# STC89C52.net
KiCad netlist of a schematic drawn in Altium Designer
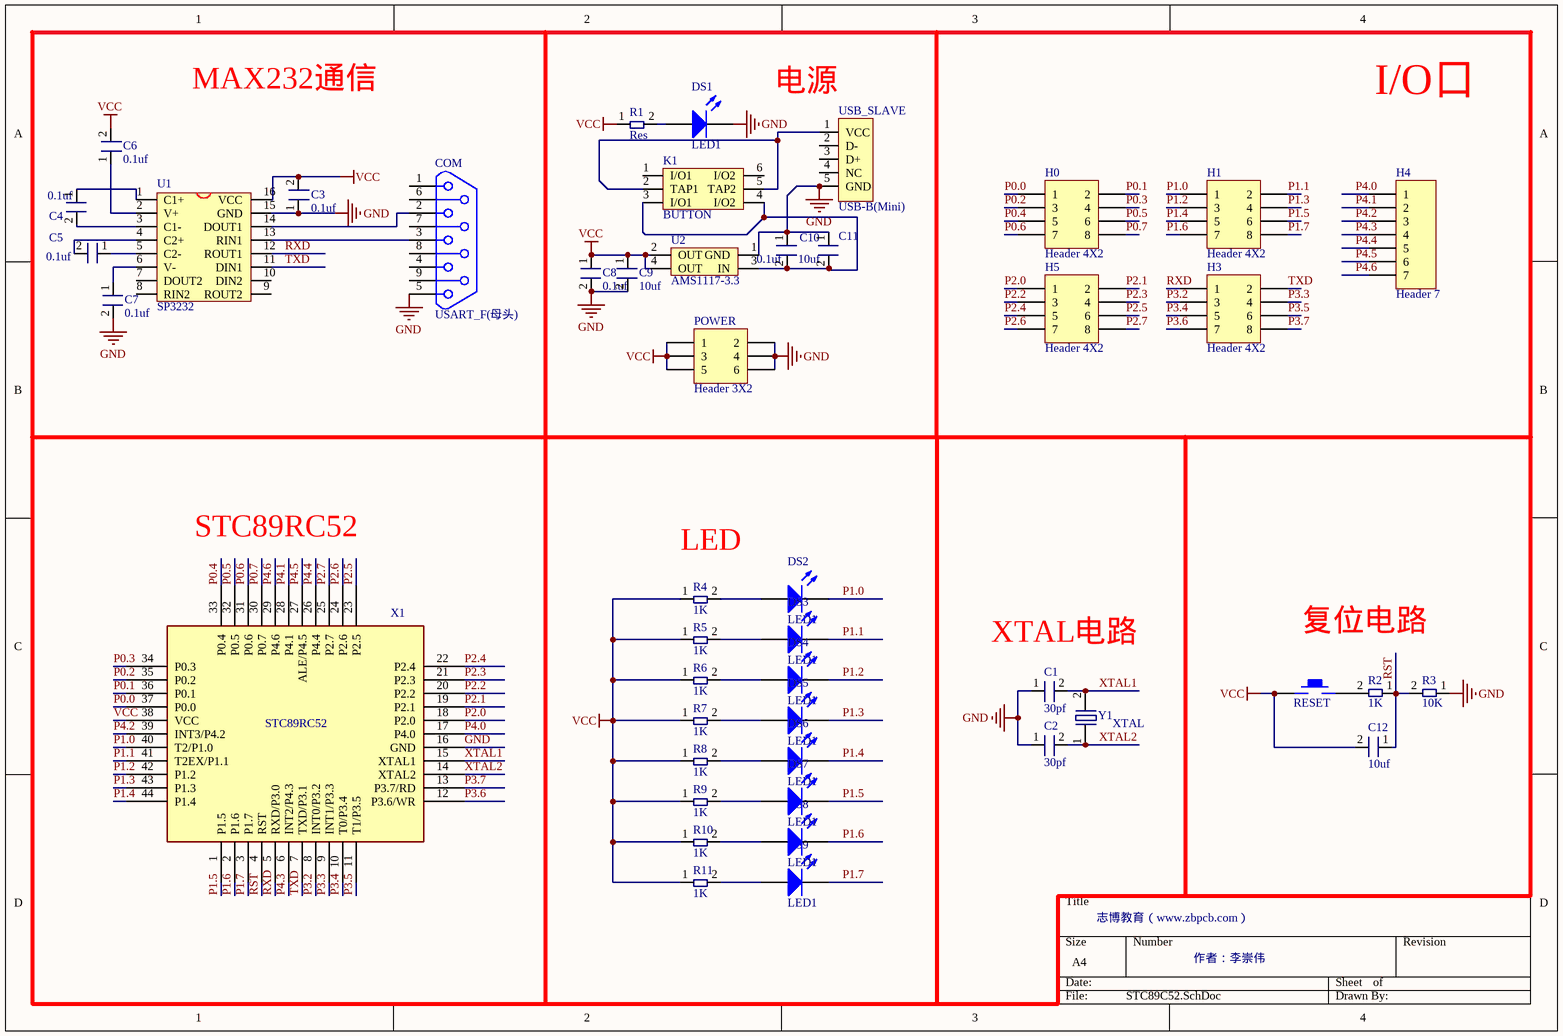
[diagram p0: STC89C52.SchDoc]

(export (version "E")
  (design (tool "Eeschema 10.0.6"))
  (components
    (comp (ref "C1") (value "30pf") (footprint "Cap") (libsource (lib "STC89C52") (part "Cap")))
    (comp (ref "C2") (value "30pf") (footprint "Cap") (libsource (lib "STC89C52") (part "Cap")))
    (comp (ref "C3") (value "0.1uf") (footprint "Cap") (libsource (lib "STC89C52") (part "Cap")))
    (comp (ref "C4") (value "0.1uf") (footprint "Cap") (libsource (lib "STC89C52") (part "Cap")))
    (comp (ref "C5") (value "0.1uf") (footprint "Cap") (libsource (lib "STC89C52") (part "Cap")))
    (comp (ref "C6") (value "0.1uf") (footprint "Cap") (libsource (lib "STC89C52") (part "Cap")))
    (comp (ref "C7") (value "0.1uf") (footprint "Cap") (libsource (lib "STC89C52") (part "Cap")))
    (comp (ref "C8") (value "0.1uf") (footprint "Cap") (libsource (lib "STC89C52") (part "Cap")))
    (comp (ref "C9") (value "10uf") (footprint "Cap") (libsource (lib "STC89C52") (part "Cap")))
    (comp (ref "C10") (value "0.1uf") (footprint "Cap") (libsource (lib "STC89C52") (part "Cap")))
    (comp (ref "C11") (value "10uf") (footprint "Cap") (libsource (lib "STC89C52") (part "Cap")))
    (comp (ref "C12") (value "10uf") (footprint "Cap") (libsource (lib "STC89C52") (part "Cap")))
    (comp (ref "COM") (value "USART_F(母头)") (footprint "DB9") (libsource (lib "STM32F407封装库") (part "DB9")))
    (comp (ref "DS1")
      (value "LED1")
      (footprint "SMDLED")
      (description "Typical RED, GREEN, YELLOW, AMBER GaAs LED")
      (fields (field (name "PUBLISHER") "Altium Limited"))
      (libsource (lib "STM32F407封装库") (part "LED2"))
    )
    (comp (ref "DS2")
      (value "LED1")
      (footprint "SMDLED")
      (description "Typical RED, GREEN, YELLOW, AMBER GaAs LED")
      (fields (field (name "PUBLISHER") "Altium Limited"))
      (libsource (lib "STM32F407封装库") (part "LED2"))
    )
    (comp (ref "DS3")
      (value "LED1")
      (footprint "SMDLED")
      (description "Typical RED, GREEN, YELLOW, AMBER GaAs LED")
      (fields (field (name "PUBLISHER") "Altium Limited"))
      (libsource (lib "STM32F407封装库") (part "LED2"))
    )
    (comp (ref "DS4")
      (value "LED1")
      (footprint "SMDLED")
      (description "Typical RED, GREEN, YELLOW, AMBER GaAs LED")
      (fields (field (name "PUBLISHER") "Altium Limited"))
      (libsource (lib "STM32F407封装库") (part "LED2"))
    )
    (comp (ref "DS5")
      (value "LED1")
      (footprint "SMDLED")
      (description "Typical RED, GREEN, YELLOW, AMBER GaAs LED")
      (fields (field (name "PUBLISHER") "Altium Limited"))
      (libsource (lib "STM32F407封装库") (part "LED2"))
    )
    (comp (ref "DS6")
      (value "LED1")
      (footprint "SMDLED")
      (description "Typical RED, GREEN, YELLOW, AMBER GaAs LED")
      (fields (field (name "PUBLISHER") "Altium Limited"))
      (libsource (lib "STM32F407封装库") (part "LED2"))
    )
    (comp (ref "DS7")
      (value "LED1")
      (footprint "SMDLED")
      (description "Typical RED, GREEN, YELLOW, AMBER GaAs LED")
      (fields (field (name "PUBLISHER") "Altium Limited"))
      (libsource (lib "STM32F407封装库") (part "LED2"))
    )
    (comp (ref "DS8")
      (value "LED1")
      (footprint "SMDLED")
      (description "Typical RED, GREEN, YELLOW, AMBER GaAs LED")
      (fields (field (name "PUBLISHER") "Altium Limited"))
      (libsource (lib "STM32F407封装库") (part "LED2"))
    )
    (comp (ref "DS9")
      (value "LED1")
      (footprint "SMDLED")
      (description "Typical RED, GREEN, YELLOW, AMBER GaAs LED")
      (fields (field (name "PUBLISHER") "Altium Limited"))
      (libsource (lib "STM32F407封装库") (part "LED2"))
    )
    (comp (ref "H0")
      (value "Header 4X2")
      (footprint "HDR2X4")
      (description "Header, 4-Pin, Dual row")
      (fields (field (name "PUBLISHER") "Altium Limited"))
      (libsource (lib "Miscellaneous Connectors") (part "Header 4X2"))
    )
    (comp (ref "H1")
      (value "Header 4X2")
      (footprint "HDR2X4")
      (description "Header, 4-Pin, Dual row")
      (fields (field (name "PUBLISHER") "Altium Limited"))
      (libsource (lib "Miscellaneous Connectors") (part "Header 4X2"))
    )
    (comp (ref "H3")
      (value "Header 4X2")
      (footprint "HDR2X4")
      (description "Header, 4-Pin, Dual row")
      (fields (field (name "PUBLISHER") "Altium Limited"))
      (libsource (lib "Miscellaneous Connectors") (part "Header 4X2"))
    )
    (comp (ref "H4")
      (value "Header 7")
      (footprint "HDR1X7")
      (description "Header, 7-Pin")
      (fields (field (name "PUBLISHER") "Altium Limited"))
      (libsource (lib "Miscellaneous Connectors") (part "Header 7"))
    )
    (comp (ref "H5")
      (value "Header 4X2")
      (footprint "HDR2X4")
      (description "Header, 4-Pin, Dual row")
      (fields (field (name "PUBLISHER") "Altium Limited"))
      (libsource (lib "Miscellaneous Connectors") (part "Header 4X2"))
    )
    (comp (ref "K1")
      (value "BUTTON")
      (footprint "BTN8.5*8.5")
      (libsource (lib "STM32F407封装库") (part "BUTTON"))
    )
    (comp (ref "POWER")
      (value "Header 3X2")
      (footprint "HDR2X3")
      (description "Header, 3-Pin, Dual row")
      (fields (field (name "PUBLISHER") "Altium Limited"))
      (libsource (lib "STM32F407封装库") (part "Header 3X2"))
    )
    (comp (ref "R1") (value "Res") (footprint "Cap") (libsource (lib "STC89C52") (part "Res")))
    (comp (ref "R2") (value "1K") (footprint "Cap") (libsource (lib "STC89C52") (part "Res")))
    (comp (ref "R3") (value "10K") (footprint "Cap") (libsource (lib "STC89C52") (part "Res")))
    (comp (ref "R4") (value "1K") (footprint "Cap") (libsource (lib "STC89C52") (part "Res")))
    (comp (ref "R5") (value "1K") (footprint "Cap") (libsource (lib "STC89C52") (part "Res")))
    (comp (ref "R6") (value "1K") (footprint "Cap") (libsource (lib "STC89C52") (part "Res")))
    (comp (ref "R7") (value "1K") (footprint "Cap") (libsource (lib "STC89C52") (part "Res")))
    (comp (ref "R8") (value "1K") (footprint "Cap") (libsource (lib "STC89C52") (part "Res")))
    (comp (ref "R9") (value "1K") (footprint "Cap") (libsource (lib "STC89C52") (part "Res")))
    (comp (ref "R10") (value "1K") (footprint "Cap") (libsource (lib "STC89C52") (part "Res")))
    (comp (ref "R11") (value "1K") (footprint "Cap") (libsource (lib "STC89C52") (part "Res")))
    (comp (ref "RESET") (value "KEY_M") (footprint "KEY_M") (libsource (lib "STM32F407封装库") (part "KEY_M")))
    (comp (ref "U1") (value "SP3232") (footprint "SOP16M") (libsource (lib "STM32F407封装库") (part "MAX3232")))
    (comp (ref "U2")
      (value "AMS1117-3.3")
      (footprint "AMS1117")
      (libsource (lib "STM32F407封装库") (part "AMS1117"))
    )
    (comp (ref "USB_SLAVE")
      (value "USB-B(Mini)")
      (footprint "USB/SM0.8-6H5")
      (libsource (lib "STM32F407封装库") (part "USB5"))
    )
    (comp (ref "X1")
      (value "STC89RC52")
      (footprint "STC89C52")
      (libsource (lib "STC89C52") (part "STC89RC52"))
    )
    (comp (ref "Y1") (value "XTAL") (footprint "XTAL") (libsource (lib "STC89C52") (part "XTAL")))
  )
  (nets
    (net (code "1") (name "/P0.0") (class "Default")
      (node (ref "H0") (pin "1") (pinfunction "1_1") (pintype "passive"))
      (node (ref "X1") (pin "37") (pinfunction "P0.0_37") (pintype "passive"))
    )
    (net (code "2") (name "/P0.1") (class "Default")
      (node (ref "H0") (pin "2") (pinfunction "2_2") (pintype "passive"))
      (node (ref "X1") (pin "36") (pinfunction "P0.1_36") (pintype "passive"))
    )
    (net (code "3") (name "/P0.2") (class "Default")
      (node (ref "H0") (pin "3") (pinfunction "3_3") (pintype "passive"))
      (node (ref "X1") (pin "35") (pinfunction "P0.2_35") (pintype "passive"))
    )
    (net (code "4") (name "/P0.3") (class "Default")
      (node (ref "H0") (pin "4") (pinfunction "4_4") (pintype "passive"))
      (node (ref "X1") (pin "34") (pinfunction "P0.3_34") (pintype "passive"))
    )
    (net (code "5") (name "/P0.4") (class "Default")
      (node (ref "H0") (pin "5") (pinfunction "5_5") (pintype "passive"))
      (node (ref "X1") (pin "33") (pinfunction "P0.4_33") (pintype "passive"))
    )
    (net (code "6") (name "/P0.5") (class "Default")
      (node (ref "H0") (pin "6") (pinfunction "6_6") (pintype "passive"))
      (node (ref "X1") (pin "32") (pinfunction "P0.5_32") (pintype "passive"))
    )
    (net (code "7") (name "/P0.6") (class "Default")
      (node (ref "H0") (pin "7") (pinfunction "7_7") (pintype "passive"))
      (node (ref "X1") (pin "31") (pinfunction "P0.6_31") (pintype "passive"))
    )
    (net (code "8") (name "/P0.7") (class "Default")
      (node (ref "H0") (pin "8") (pinfunction "8_8") (pintype "passive"))
      (node (ref "X1") (pin "30") (pinfunction "P0.7_30") (pintype "passive"))
    )
    (net (code "9") (name "/P1.0") (class "Default")
      (node (ref "DS2") (pin "2") (pinfunction "K_2") (pintype "passive"))
      (node (ref "H1") (pin "1") (pinfunction "1_1") (pintype "passive"))
      (node (ref "X1") (pin "40") (pinfunction "T2/P1.0_40") (pintype "passive"))
    )
    (net (code "10") (name "/P1.1") (class "Default")
      (node (ref "DS3") (pin "2") (pinfunction "K_2") (pintype "passive"))
      (node (ref "H1") (pin "2") (pinfunction "2_2") (pintype "passive"))
      (node (ref "X1") (pin "41") (pinfunction "T2EX/P1.1_41") (pintype "passive"))
    )
    (net (code "11") (name "/P1.2") (class "Default")
      (node (ref "DS4") (pin "2") (pinfunction "K_2") (pintype "passive"))
      (node (ref "H1") (pin "3") (pinfunction "3_3") (pintype "passive"))
      (node (ref "X1") (pin "42") (pinfunction "P1.2_42") (pintype "passive"))
    )
    (net (code "12") (name "/P1.3") (class "Default")
      (node (ref "DS5") (pin "2") (pinfunction "K_2") (pintype "passive"))
      (node (ref "H1") (pin "4") (pinfunction "4_4") (pintype "passive"))
      (node (ref "X1") (pin "43") (pinfunction "P1.3_43") (pintype "passive"))
    )
    (net (code "13") (name "/P1.4") (class "Default")
      (node (ref "DS6") (pin "2") (pinfunction "K_2") (pintype "passive"))
      (node (ref "H1") (pin "5") (pinfunction "5_5") (pintype "passive"))
      (node (ref "X1") (pin "44") (pinfunction "P1.4_44") (pintype "passive"))
    )
    (net (code "14") (name "/P1.5") (class "Default")
      (node (ref "DS7") (pin "2") (pinfunction "K_2") (pintype "passive"))
      (node (ref "H1") (pin "6") (pinfunction "6_6") (pintype "passive"))
      (node (ref "X1") (pin "1") (pinfunction "P1.5_1") (pintype "passive"))
    )
    (net (code "15") (name "/P1.6") (class "Default")
      (node (ref "DS8") (pin "2") (pinfunction "K_2") (pintype "passive"))
      (node (ref "H1") (pin "7") (pinfunction "7_7") (pintype "passive"))
      (node (ref "X1") (pin "2") (pinfunction "P1.6_2") (pintype "passive"))
    )
    (net (code "16") (name "/P1.7") (class "Default")
      (node (ref "DS9") (pin "2") (pinfunction "K_2") (pintype "passive"))
      (node (ref "H1") (pin "8") (pinfunction "8_8") (pintype "passive"))
      (node (ref "X1") (pin "3") (pinfunction "P1.7_3") (pintype "passive"))
    )
    (net (code "17") (name "/P2.0") (class "Default")
      (node (ref "H5") (pin "1") (pinfunction "1_1") (pintype "passive"))
      (node (ref "X1") (pin "18") (pinfunction "P2.0_18") (pintype "passive"))
    )
    (net (code "18") (name "/P2.1") (class "Default")
      (node (ref "H5") (pin "2") (pinfunction "2_2") (pintype "passive"))
      (node (ref "X1") (pin "19") (pinfunction "P2.1_19") (pintype "passive"))
    )
    (net (code "19") (name "/P2.2") (class "Default")
      (node (ref "H5") (pin "3") (pinfunction "3_3") (pintype "passive"))
      (node (ref "X1") (pin "20") (pinfunction "P2.2_20") (pintype "passive"))
    )
    (net (code "20") (name "/P2.3") (class "Default")
      (node (ref "H5") (pin "4") (pinfunction "4_4") (pintype "passive"))
      (node (ref "X1") (pin "21") (pinfunction "P2.3_21") (pintype "passive"))
    )
    (net (code "21") (name "/P2.4") (class "Default")
      (node (ref "H5") (pin "5") (pinfunction "5_5") (pintype "passive"))
      (node (ref "X1") (pin "22") (pinfunction "P2.4_22") (pintype "passive"))
    )
    (net (code "22") (name "/P2.5") (class "Default")
      (node (ref "H5") (pin "6") (pinfunction "6_6") (pintype "passive"))
      (node (ref "X1") (pin "23") (pinfunction "P2.5_23") (pintype "passive"))
    )
    (net (code "23") (name "/P2.6") (class "Default")
      (node (ref "H5") (pin "7") (pinfunction "7_7") (pintype "passive"))
      (node (ref "X1") (pin "24") (pinfunction "P2.6_24") (pintype "passive"))
    )
    (net (code "24") (name "/P2.7") (class "Default")
      (node (ref "H5") (pin "8") (pinfunction "8_8") (pintype "passive"))
      (node (ref "X1") (pin "25") (pinfunction "P2.7_25") (pintype "passive"))
    )
    (net (code "25") (name "/P3.2") (class "Default")
      (node (ref "H3") (pin "3") (pinfunction "3_3") (pintype "passive"))
      (node (ref "X1") (pin "8") (pinfunction "INT0/P3.2_8") (pintype "passive"))
    )
    (net (code "26") (name "/P3.3") (class "Default")
      (node (ref "H3") (pin "4") (pinfunction "4_4") (pintype "passive"))
      (node (ref "X1") (pin "9") (pinfunction "INT1/P3.3_9") (pintype "passive"))
    )
    (net (code "27") (name "/P3.4") (class "Default")
      (node (ref "H3") (pin "5") (pinfunction "5_5") (pintype "passive"))
      (node (ref "X1") (pin "10") (pinfunction "T0/P3.4_10") (pintype "passive"))
    )
    (net (code "28") (name "/P3.5") (class "Default")
      (node (ref "H3") (pin "6") (pinfunction "6_6") (pintype "passive"))
      (node (ref "X1") (pin "11") (pinfunction "T1/P3.5_11") (pintype "passive"))
    )
    (net (code "29") (name "/P3.6") (class "Default")
      (node (ref "H3") (pin "7") (pinfunction "7_7") (pintype "passive"))
      (node (ref "X1") (pin "12") (pinfunction "P3.6/WR_12") (pintype "passive"))
    )
    (net (code "30") (name "/P3.7") (class "Default")
      (node (ref "H3") (pin "8") (pinfunction "8_8") (pintype "passive"))
      (node (ref "X1") (pin "13") (pinfunction "P3.7/RD_13") (pintype "passive"))
    )
    (net (code "31") (name "/P4.0") (class "Default")
      (node (ref "H4") (pin "1") (pinfunction "1_1") (pintype "passive"))
      (node (ref "X1") (pin "17") (pinfunction "P4.0_17") (pintype "passive"))
    )
    (net (code "32") (name "/P4.1") (class "Default")
      (node (ref "H4") (pin "2") (pinfunction "2_2") (pintype "passive"))
      (node (ref "X1") (pin "28") (pinfunction "P4.1_28") (pintype "passive"))
    )
    (net (code "33") (name "/P4.2") (class "Default")
      (node (ref "H4") (pin "3") (pinfunction "3_3") (pintype "passive"))
      (node (ref "X1") (pin "39") (pinfunction "INT3/P4.2_39") (pintype "passive"))
    )
    (net (code "34") (name "/P4.3") (class "Default")
      (node (ref "H4") (pin "4") (pinfunction "4_4") (pintype "passive"))
      (node (ref "X1") (pin "6") (pinfunction "INT2/P4.3_6") (pintype "passive"))
    )
    (net (code "35") (name "/P4.4") (class "Default")
      (node (ref "H4") (pin "5") (pinfunction "5_5") (pintype "passive"))
      (node (ref "X1") (pin "26") (pinfunction "P4.4_26") (pintype "passive"))
    )
    (net (code "36") (name "/P4.5") (class "Default")
      (node (ref "H4") (pin "6") (pinfunction "6_6") (pintype "passive"))
      (node (ref "X1") (pin "27") (pinfunction "ALE/P4.5_27") (pintype "passive"))
    )
    (net (code "37") (name "/P4.6") (class "Default")
      (node (ref "H4") (pin "7") (pinfunction "7_7") (pintype "passive"))
      (node (ref "X1") (pin "29") (pinfunction "P4.6_29") (pintype "passive"))
    )
    (net (code "38") (name "/RST") (class "Default")
      (node (ref "C12") (pin "1") (pinfunction "1_1") (pintype "passive"))
      (node (ref "R2") (pin "1") (pinfunction "60_1") (pintype "passive"))
      (node (ref "R3") (pin "2") (pinfunction "59_2") (pintype "passive"))
      (node (ref "X1") (pin "4") (pinfunction "RST_4") (pintype "passive"))
    )
    (net (code "39") (name "/RXD") (class "Default")
      (node (ref "H3") (pin "1") (pinfunction "1_1") (pintype "passive"))
      (node (ref "U1") (pin "12") (pinfunction "ROUT1_12") (pintype "passive"))
      (node (ref "X1") (pin "5") (pinfunction "RXD/P3.0_5") (pintype "passive"))
    )
    (net (code "40") (name "/TXD") (class "Default")
      (node (ref "H3") (pin "2") (pinfunction "2_2") (pintype "passive"))
      (node (ref "U1") (pin "11") (pinfunction "DIN1_11") (pintype "passive"))
      (node (ref "X1") (pin "7") (pinfunction "TXD/P3.1_7") (pintype "passive"))
    )
    (net (code "41") (name "/XTAL1") (class "Default")
      (node (ref "C1") (pin "2") (pinfunction "2_2") (pintype "passive"))
      (node (ref "X1") (pin "15") (pinfunction "XTAL1_15") (pintype "passive"))
      (node (ref "Y1") (pin "2") (pinfunction "56_2") (pintype "passive"))
    )
    (net (code "42") (name "/XTAL2") (class "Default")
      (node (ref "C2") (pin "2") (pinfunction "2_2") (pintype "passive"))
      (node (ref "X1") (pin "14") (pinfunction "XTAL2_14") (pintype "passive"))
      (node (ref "Y1") (pin "1") (pinfunction "55_1") (pintype "passive"))
    )
    (net (code "43") (name "GND") (class "Default")
      (node (ref "C1") (pin "1") (pinfunction "1_1") (pintype "passive"))
      (node (ref "C10") (pin "1") (pinfunction "1_1") (pintype "passive"))
      (node (ref "C11") (pin "1") (pinfunction "1_1") (pintype "passive"))
      (node (ref "C2") (pin "1") (pinfunction "1_1") (pintype "passive"))
      (node (ref "C3") (pin "1") (pinfunction "1_1") (pintype "passive"))
      (node (ref "C7") (pin "2") (pinfunction "2_2") (pintype "passive"))
      (node (ref "C8") (pin "2") (pinfunction "2_2") (pintype "passive"))
      (node (ref "C9") (pin "2") (pinfunction "2_2") (pintype "passive"))
      (node (ref "COM") (pin "5") (pinfunction "5_5") (pintype "passive"))
      (node (ref "DS1") (pin "2") (pinfunction "K_2") (pintype "passive"))
      (node (ref "POWER") (pin "2") (pinfunction "2_2") (pintype "passive"))
      (node (ref "POWER") (pin "4") (pinfunction "4_4") (pintype "passive"))
      (node (ref "POWER") (pin "6") (pinfunction "6_6") (pintype "passive"))
      (node (ref "R3") (pin "1") (pinfunction "60_1") (pintype "passive"))
      (node (ref "U1") (pin "15") (pinfunction "GND_15") (pintype "passive"))
      (node (ref "U2") (pin "1") (pinfunction "GND_1") (pintype "passive"))
      (node (ref "USB_SLAVE") (pin "5") (pinfunction "GND_5") (pintype "passive"))
      (node (ref "X1") (pin "16") (pinfunction "GND_16") (pintype "passive"))
    )
    (net (code "44") (name "Net-(DS1-A)") (class "Default")
      (node (ref "DS1") (pin "1") (pinfunction "A_1") (pintype "passive"))
      (node (ref "R1") (pin "2") (pinfunction "59_2") (pintype "passive"))
    )
    (net (code "45") (name "Net-(DS2-A)") (class "Default")
      (node (ref "DS2") (pin "1") (pinfunction "A_1") (pintype "passive"))
      (node (ref "R4") (pin "2") (pinfunction "59_2") (pintype "passive"))
    )
    (net (code "46") (name "Net-(DS3-A)") (class "Default")
      (node (ref "DS3") (pin "1") (pinfunction "A_1") (pintype "passive"))
      (node (ref "R5") (pin "2") (pinfunction "59_2") (pintype "passive"))
    )
    (net (code "47") (name "Net-(DS4-A)") (class "Default")
      (node (ref "DS4") (pin "1") (pinfunction "A_1") (pintype "passive"))
      (node (ref "R6") (pin "2") (pinfunction "59_2") (pintype "passive"))
    )
    (net (code "48") (name "Net-(DS5-A)") (class "Default")
      (node (ref "DS5") (pin "1") (pinfunction "A_1") (pintype "passive"))
      (node (ref "R7") (pin "2") (pinfunction "59_2") (pintype "passive"))
    )
    (net (code "49") (name "Net-(DS6-A)") (class "Default")
      (node (ref "DS6") (pin "1") (pinfunction "A_1") (pintype "passive"))
      (node (ref "R8") (pin "2") (pinfunction "59_2") (pintype "passive"))
    )
    (net (code "50") (name "Net-(DS7-A)") (class "Default")
      (node (ref "DS7") (pin "1") (pinfunction "A_1") (pintype "passive"))
      (node (ref "R9") (pin "2") (pinfunction "59_2") (pintype "passive"))
    )
    (net (code "51") (name "Net-(DS8-A)") (class "Default")
      (node (ref "DS8") (pin "1") (pinfunction "A_1") (pintype "passive"))
      (node (ref "R10") (pin "2") (pinfunction "59_2") (pintype "passive"))
    )
    (net (code "52") (name "Net-(DS9-A)") (class "Default")
      (node (ref "DS9") (pin "1") (pinfunction "A_1") (pintype "passive"))
      (node (ref "R11") (pin "2") (pinfunction "59_2") (pintype "passive"))
    )
    (net (code "53") (name "Net-(K1-TAP1)") (class "Default")
      (node (ref "K1") (pin "2") (pinfunction "TAP1_2") (pintype "passive"))
      (node (ref "K1") (pin "5") (pinfunction "TAP2_5") (pintype "passive"))
      (node (ref "USB_SLAVE") (pin "1") (pinfunction "VCC_1") (pintype "passive"))
    )
    (net (code "54") (name "Net-(R2-59)") (class "Default")
      (node (ref "R2") (pin "2") (pinfunction "59_2") (pintype "passive"))
      (node (ref "RESET") (pin "2") (pinfunction "2_2") (pintype "passive"))
    )
    (net (code "55") (name "Net-(U1-C1+)") (class "Default")
      (node (ref "C4") (pin "1") (pinfunction "1_1") (pintype "passive"))
      (node (ref "U1") (pin "1") (pinfunction "C1+_1") (pintype "passive"))
    )
    (net (code "56") (name "Net-(U1-C1-)") (class "Default")
      (node (ref "C4") (pin "2") (pinfunction "2_2") (pintype "passive"))
      (node (ref "U1") (pin "3") (pinfunction "C1-_3") (pintype "passive"))
    )
    (net (code "57") (name "Net-(U1-C2+)") (class "Default")
      (node (ref "C5") (pin "2") (pinfunction "2_2") (pintype "passive"))
      (node (ref "U1") (pin "4") (pinfunction "C2+_4") (pintype "passive"))
    )
    (net (code "58") (name "Net-(U1-C2-)") (class "Default")
      (node (ref "C5") (pin "1") (pinfunction "1_1") (pintype "passive"))
      (node (ref "U1") (pin "5") (pinfunction "C2-_5") (pintype "passive"))
    )
    (net (code "59") (name "Net-(U1-DOUT1)") (class "Default")
      (node (ref "COM") (pin "2") (pinfunction "2_2") (pintype "passive"))
      (node (ref "U1") (pin "14") (pinfunction "DOUT1_14") (pintype "passive"))
    )
    (net (code "60") (name "Net-(U1-RIN1)") (class "Default")
      (node (ref "COM") (pin "3") (pinfunction "3_3") (pintype "passive"))
      (node (ref "U1") (pin "13") (pinfunction "RIN1_13") (pintype "passive"))
    )
    (net (code "61") (name "Net-(U1-V+)") (class "Default")
      (node (ref "C6") (pin "1") (pinfunction "1_1") (pintype "passive"))
      (node (ref "U1") (pin "2") (pinfunction "V+_2") (pintype "passive"))
    )
    (net (code "62") (name "Net-(U1-V-)") (class "Default")
      (node (ref "C7") (pin "1") (pinfunction "1_1") (pintype "passive"))
      (node (ref "U1") (pin "6") (pinfunction "V-_6") (pintype "passive"))
    )
    (net (code "63") (name "Net-(U2-IN)") (class "Default")
      (node (ref "C10") (pin "2") (pinfunction "2_2") (pintype "passive"))
      (node (ref "C11") (pin "2") (pinfunction "2_2") (pintype "passive"))
      (node (ref "K1") (pin "3") (pinfunction "I/O1_3") (pintype "passive"))
      (node (ref "K1") (pin "4") (pinfunction "I/O2_4") (pintype "passive"))
      (node (ref "U2") (pin "3") (pinfunction "IN_3") (pintype "passive"))
    )
    (net (code "64") (name "VCC") (class "Default")
      (node (ref "C12") (pin "2") (pinfunction "2_2") (pintype "passive"))
      (node (ref "C3") (pin "2") (pinfunction "2_2") (pintype "passive"))
      (node (ref "C6") (pin "2") (pinfunction "2_2") (pintype "passive"))
      (node (ref "C8") (pin "1") (pinfunction "1_1") (pintype "passive"))
      (node (ref "C9") (pin "1") (pinfunction "1_1") (pintype "passive"))
      (node (ref "POWER") (pin "1") (pinfunction "1_1") (pintype "passive"))
      (node (ref "POWER") (pin "3") (pinfunction "3_3") (pintype "passive"))
      (node (ref "POWER") (pin "5") (pinfunction "5_5") (pintype "passive"))
      (node (ref "R1") (pin "1") (pinfunction "60_1") (pintype "passive"))
      (node (ref "R10") (pin "1") (pinfunction "60_1") (pintype "passive"))
      (node (ref "R11") (pin "1") (pinfunction "60_1") (pintype "passive"))
      (node (ref "R4") (pin "1") (pinfunction "60_1") (pintype "passive"))
      (node (ref "R5") (pin "1") (pinfunction "60_1") (pintype "passive"))
      (node (ref "R6") (pin "1") (pinfunction "60_1") (pintype "passive"))
      (node (ref "R7") (pin "1") (pinfunction "60_1") (pintype "passive"))
      (node (ref "R8") (pin "1") (pinfunction "60_1") (pintype "passive"))
      (node (ref "R9") (pin "1") (pinfunction "60_1") (pintype "passive"))
      (node (ref "RESET") (pin "1") (pinfunction "1_1") (pintype "passive"))
      (node (ref "U1") (pin "16") (pinfunction "VCC_16") (pintype "passive"))
      (node (ref "U2") (pin "2") (pinfunction "OUT_2") (pintype "passive"))
      (node (ref "U2") (pin "4") (pinfunction "OUT_4") (pintype "passive"))
      (node (ref "X1") (pin "38") (pinfunction "VCC_38") (pintype "passive"))
    )
    (net (code "65") (name "unconnected-(COM-Pad1)") (class "Default")
      (node (ref "COM") (pin "1") (pinfunction "1_1") (pintype "passive"))
    )
    (net (code "66") (name "unconnected-(COM-Pad4)") (class "Default")
      (node (ref "COM") (pin "4") (pinfunction "4_4") (pintype "passive"))
    )
    (net (code "67") (name "unconnected-(COM-Pad6)") (class "Default")
      (node (ref "COM") (pin "6") (pinfunction "6_6") (pintype "passive"))
    )
    (net (code "68") (name "unconnected-(COM-Pad7)") (class "Default")
      (node (ref "COM") (pin "7") (pinfunction "7_7") (pintype "passive"))
    )
    (net (code "69") (name "unconnected-(COM-Pad8)") (class "Default")
      (node (ref "COM") (pin "8") (pinfunction "8_8") (pintype "passive"))
    )
    (net (code "70") (name "unconnected-(COM-Pad9)") (class "Default")
      (node (ref "COM") (pin "9") (pinfunction "9_9") (pintype "passive"))
    )
    (net (code "71") (name "unconnected-(K1-I{slash}O1-Pad1)") (class "Default")
      (node (ref "K1") (pin "1") (pinfunction "I/O1_1") (pintype "passive"))
    )
    (net (code "72") (name "unconnected-(K1-I{slash}O2-Pad6)") (class "Default")
      (node (ref "K1") (pin "6") (pinfunction "I/O2_6") (pintype "passive"))
    )
    (net (code "73") (name "unconnected-(U1-DIN2-Pad10)") (class "Default")
      (node (ref "U1") (pin "10") (pinfunction "DIN2_10") (pintype "passive"))
    )
    (net (code "74") (name "unconnected-(U1-DOUT2-Pad7)") (class "Default")
      (node (ref "U1") (pin "7") (pinfunction "DOUT2_7") (pintype "passive"))
    )
    (net (code "75") (name "unconnected-(U1-RIN2-Pad8)") (class "Default")
      (node (ref "U1") (pin "8") (pinfunction "RIN2_8") (pintype "passive"))
    )
    (net (code "76") (name "unconnected-(U1-ROUT2-Pad9)") (class "Default")
      (node (ref "U1") (pin "9") (pinfunction "ROUT2_9") (pintype "passive"))
    )
    (net (code "77") (name "unconnected-(USB_SLAVE-D+-Pad3)") (class "Default")
      (node (ref "USB_SLAVE") (pin "3") (pinfunction "D+_3") (pintype "passive"))
    )
    (net (code "78") (name "unconnected-(USB_SLAVE-D--Pad2)") (class "Default")
      (node (ref "USB_SLAVE") (pin "2") (pinfunction "D-_2") (pintype "passive"))
    )
    (net (code "79") (name "unconnected-(USB_SLAVE-NC-Pad4)") (class "Default")
      (node (ref "USB_SLAVE") (pin "4") (pinfunction "NC_4") (pintype "passive"))
    )
  )
)
